# power_supply.net
KiCad netlist of a schematic drawn in EAGLE
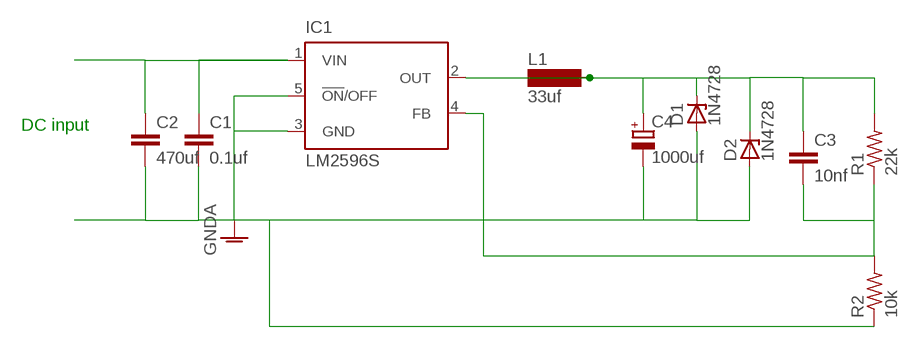
[diagram p0: schematic, sheet 1]

(export (version "E")
  (design (tool "Eeschema 10.0.6"))
  (components
    (comp (ref "C1")
      (value "0.1uf")
      (footprint "eagle-import:C2.5-3")
      (libsource (lib "eagle-import") (part "C2,5-3"))
    )
    (comp (ref "C2")
      (value "470uf")
      (footprint "eagle-import:C2.5-3")
      (libsource (lib "eagle-import") (part "C2,5-3"))
    )
    (comp (ref "C3")
      (value "10nf")
      (footprint "eagle-import:C2.5-3")
      (libsource (lib "eagle-import") (part "C2,5-3"))
    )
    (comp (ref "C4")
      (value "1000uf")
      (footprint "eagle-import:085CS_1AR")
      (libsource (lib "eagle-import") (part "CPOL-EU085CS-1AR"))
    )
    (comp (ref "D1")
      (value "1N4728")
      (footprint "eagle-import:DO41Z10")
      (libsource (lib "eagle-import") (part "1N4728"))
    )
    (comp (ref "D2")
      (value "1N4728")
      (footprint "eagle-import:DO41Z10")
      (libsource (lib "eagle-import") (part "1N4728"))
    )
    (comp (ref "IC1")
      (value "LM2596S")
      (footprint "eagle-import:TO263-5")
      (fields (field (name "MF") "NATIONAL SEMICONDUCTOR") (field (name "MPN") "LM2596S-ADJ/NOPB"))
      (libsource (lib "eagle-import") (part "LM2596S"))
    )
    (comp (ref "L1")
      (value "33uf")
      (footprint "eagle-import:BS11")
      (libsource (lib "eagle-import") (part "BS11"))
    )
    (comp (ref "R1")
      (value "22k")
      (footprint "eagle-import:0204V")
      (libsource (lib "eagle-import") (part "R-US_0204/2V"))
    )
    (comp (ref "R2")
      (value "10k")
      (footprint "eagle-import:0204V")
      (libsource (lib "eagle-import") (part "R-US_0204/2V"))
    )
  )
  (nets
    (net (code "1") (name "GNDA") (class "Default")
      (node (ref "C1") (pin "2") (pinfunction "2_2") (pintype "passive"))
      (node (ref "C2") (pin "2") (pinfunction "2_2") (pintype "passive"))
      (node (ref "C4") (pin "-") (pinfunction "-_-") (pintype "passive"))
      (node (ref "D1") (pin "A") (pinfunction "A_A") (pintype "passive"))
      (node (ref "D2") (pin "A") (pinfunction "A_A") (pintype "passive"))
      (node (ref "IC1") (pin "3") (pinfunction "GND_3") (pintype "power_in"))
      (node (ref "IC1") (pin "5") (pinfunction "~{ON}/OFF_5") (pintype "input"))
      (node (ref "R2") (pin "1") (pinfunction "1_1") (pintype "passive"))
    )
    (net (code "2") (name "Net-(IC1-FB)") (class "Default")
      (node (ref "C3") (pin "2") (pinfunction "2_2") (pintype "passive"))
      (node (ref "IC1") (pin "4") (pinfunction "FB_4") (pintype "input"))
      (node (ref "R1") (pin "1") (pinfunction "1_1") (pintype "passive"))
      (node (ref "R2") (pin "2") (pinfunction "2_2") (pintype "passive"))
    )
    (net (code "3") (name "Net-(IC1-OUT)") (class "Default")
      (node (ref "C3") (pin "1") (pinfunction "1_1") (pintype "passive"))
      (node (ref "C4") (pin "+") (pinfunction "+_+") (pintype "passive"))
      (node (ref "D1") (pin "C") (pinfunction "C_C") (pintype "passive"))
      (node (ref "D2") (pin "C") (pinfunction "C_C") (pintype "passive"))
      (node (ref "IC1") (pin "2") (pinfunction "OUT_2") (pintype "output"))
      (node (ref "L1") (pin "1") (pinfunction "1_1") (pintype "passive"))
      (node (ref "L1") (pin "2") (pinfunction "2_2") (pintype "passive"))
      (node (ref "R1") (pin "2") (pinfunction "2_2") (pintype "passive"))
    )
    (net (code "4") (name "Net-(IC1-VIN)") (class "Default")
      (node (ref "C1") (pin "1") (pinfunction "1_1") (pintype "passive"))
      (node (ref "C2") (pin "1") (pinfunction "1_1") (pintype "passive"))
      (node (ref "IC1") (pin "1") (pinfunction "VIN_1") (pintype "input"))
    )
  )
)
